# PCM2704_Test_v1B.net
KiCad netlist of a schematic drawn in EAGLE
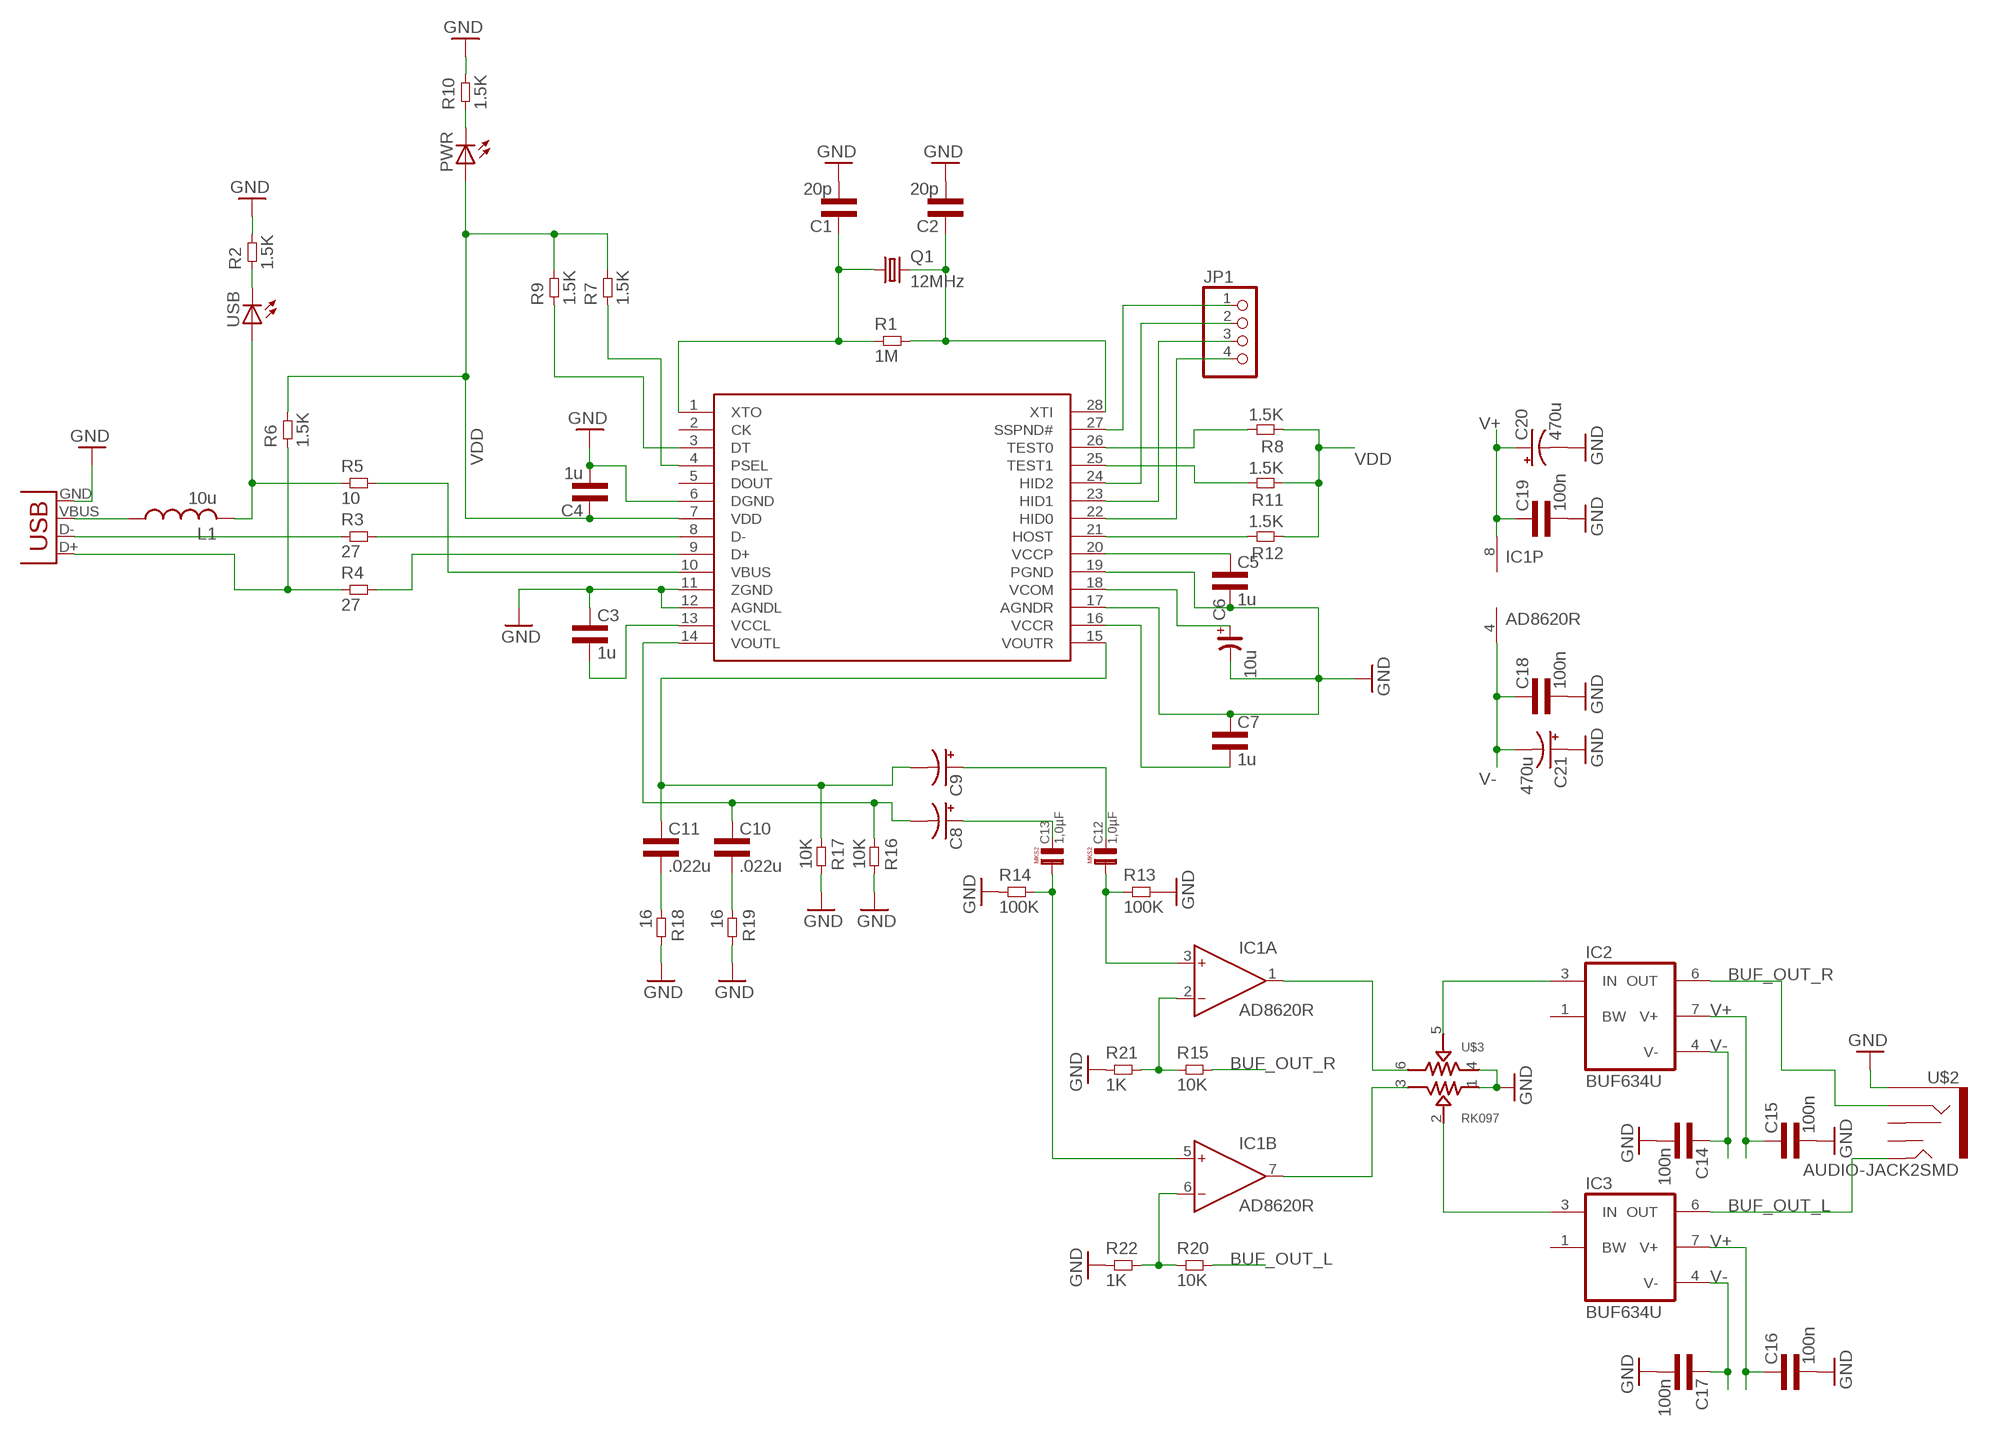
[diagram p0: schematic, sheet 1]

(export (version "E")
  (design (tool "Eeschema 10.0.6"))
  (components
    (comp (ref "C1")
      (value "20p")
      (footprint "eagle-import:0603L3")
      (libsource (lib "eagle-import") (part "CAP0603L3"))
    )
    (comp (ref "C2")
      (value "20p")
      (footprint "eagle-import:0603L3")
      (libsource (lib "eagle-import") (part "CAP0603L3"))
    )
    (comp (ref "C3")
      (value "1u")
      (footprint "eagle-import:0603L3")
      (libsource (lib "eagle-import") (part "CAP0603L3"))
    )
    (comp (ref "C4")
      (value "1u")
      (footprint "eagle-import:0603L3")
      (libsource (lib "eagle-import") (part "CAP0603L3"))
    )
    (comp (ref "C5")
      (value "1u")
      (footprint "eagle-import:0603L3")
      (libsource (lib "eagle-import") (part "CAP0603L3"))
    )
    (comp (ref "C6")
      (value "10u")
      (footprint "eagle-import:CE-010X030")
      (libsource (lib "eagle-import") (part "CP_E-010X030"))
    )
    (comp (ref "C7")
      (value "1u")
      (footprint "eagle-import:0603L3")
      (libsource (lib "eagle-import") (part "CAP0603L3"))
    )
    (comp (ref "C8")
      (value "CPOL-USE1.8-4")
      (footprint "eagle-import:E1,8-4")
      (libsource (lib "eagle-import") (part "CPOL-USE1.8-4"))
    )
    (comp (ref "C9")
      (value "CPOL-USE1.8-4")
      (footprint "eagle-import:E1,8-4")
      (libsource (lib "eagle-import") (part "CPOL-USE1.8-4"))
    )
    (comp (ref "C10")
      (value ".022u")
      (footprint "eagle-import:0603L3")
      (libsource (lib "eagle-import") (part "CAP0603L3"))
    )
    (comp (ref "C11")
      (value ".022u")
      (footprint "eagle-import:0603L3")
      (libsource (lib "eagle-import") (part "CAP0603L3"))
    )
    (comp (ref "C12")
      (value "1,0µF")
      (footprint "eagle-import:R5B5")
      (libsource (lib "eagle-import") (part "1,0µF"))
    )
    (comp (ref "C13")
      (value "1,0µF")
      (footprint "eagle-import:R5B5")
      (libsource (lib "eagle-import") (part "1,0µF"))
    )
    (comp (ref "C14")
      (value "100n")
      (footprint "eagle-import:0603L3")
      (libsource (lib "eagle-import") (part "CAP0603L3"))
    )
    (comp (ref "C15")
      (value "100n")
      (footprint "eagle-import:0603L3")
      (libsource (lib "eagle-import") (part "CAP0603L3"))
    )
    (comp (ref "C16")
      (value "100n")
      (footprint "eagle-import:0603L3")
      (libsource (lib "eagle-import") (part "CAP0603L3"))
    )
    (comp (ref "C17")
      (value "100n")
      (footprint "eagle-import:0603L3")
      (libsource (lib "eagle-import") (part "CAP0603L3"))
    )
    (comp (ref "C18")
      (value "100n")
      (footprint "eagle-import:0603L3")
      (libsource (lib "eagle-import") (part "CAP0603L3"))
    )
    (comp (ref "C19")
      (value "100n")
      (footprint "eagle-import:0603L3")
      (libsource (lib "eagle-import") (part "CAP0603L3"))
    )
    (comp (ref "C20")
      (value "470u")
      (footprint "eagle-import:E5-13")
      (libsource (lib "eagle-import") (part "CPOL-USE5-13"))
    )
    (comp (ref "C21")
      (value "470u")
      (footprint "eagle-import:E5-13")
      (libsource (lib "eagle-import") (part "CPOL-USE5-13"))
    )
    (comp (ref "IC1")
      (value "AD8620R")
      (footprint "eagle-import:SO8")
      (fields (field (name "MF") "ALTERA CORPORATION") (field (name "MPN") "AD8620ARZ"))
      (libsource (lib "eagle-import") (part "AD8620R"))
    )
    (comp (ref "IC2")
      (value "BUF634U")
      (footprint "eagle-import:SO08")
      (fields (field (name "MF") "TEXAS INSTRUMENTS"))
      (libsource (lib "eagle-import") (part "BUF634U"))
    )
    (comp (ref "IC3")
      (value "BUF634U")
      (footprint "eagle-import:SO08")
      (fields (field (name "MF") "TEXAS INSTRUMENTS"))
      (libsource (lib "eagle-import") (part "BUF634U"))
    )
    (comp (ref "JP1")
      (value "PINHD-1X4")
      (footprint "eagle-import:1X04")
      (libsource (lib "eagle-import") (part "PINHD-1X4"))
    )
    (comp (ref "L1")
      (value "10u")
      (footprint "eagle-import:L3225M")
      (libsource (lib "eagle-import") (part "L-USL3225M"))
    )
    (comp (ref "PWR")
      (value "LEDCHIP-LED0603")
      (footprint "eagle-import:CHIP-LED0603")
      (libsource (lib "eagle-import") (part "LEDCHIP-LED0603"))
    )
    (comp (ref "Q1")
      (value "12MHz")
      (footprint "eagle-import:HC49US")
      (libsource (lib "eagle-import") (part "CRYSTALHC49US"))
    )
    (comp (ref "R1")
      (value "1M")
      (footprint "eagle-import:0603L3")
      (libsource (lib "eagle-import") (part "RES0603L3"))
    )
    (comp (ref "R2")
      (value "1.5K")
      (footprint "eagle-import:0603L3")
      (libsource (lib "eagle-import") (part "RES0603L3"))
    )
    (comp (ref "R3")
      (value "27")
      (footprint "eagle-import:0603L3")
      (libsource (lib "eagle-import") (part "RES0603L3"))
    )
    (comp (ref "R4")
      (value "27")
      (footprint "eagle-import:0603L3")
      (libsource (lib "eagle-import") (part "RES0603L3"))
    )
    (comp (ref "R5")
      (value "10")
      (footprint "eagle-import:0805L3")
      (libsource (lib "eagle-import") (part "RES0805L3"))
    )
    (comp (ref "R6")
      (value "1.5K")
      (footprint "eagle-import:0603L3")
      (libsource (lib "eagle-import") (part "RES0603L3"))
    )
    (comp (ref "R7")
      (value "1.5K")
      (footprint "eagle-import:0603L3")
      (libsource (lib "eagle-import") (part "RES0603L3"))
    )
    (comp (ref "R8")
      (value "1.5K")
      (footprint "eagle-import:0603L3")
      (libsource (lib "eagle-import") (part "RES0603L3"))
    )
    (comp (ref "R9")
      (value "1.5K")
      (footprint "eagle-import:0603L3")
      (libsource (lib "eagle-import") (part "RES0603L3"))
    )
    (comp (ref "R10")
      (value "1.5K")
      (footprint "eagle-import:0603L3")
      (libsource (lib "eagle-import") (part "RES0603L3"))
    )
    (comp (ref "R11")
      (value "1.5K")
      (footprint "eagle-import:0603L3")
      (libsource (lib "eagle-import") (part "RES0603L3"))
    )
    (comp (ref "R12")
      (value "1.5K")
      (footprint "eagle-import:0603L3")
      (libsource (lib "eagle-import") (part "RES0603L3"))
    )
    (comp (ref "R13")
      (value "100K")
      (footprint "eagle-import:0603L3")
      (libsource (lib "eagle-import") (part "RES0603L3"))
    )
    (comp (ref "R14")
      (value "100K")
      (footprint "eagle-import:0603L3")
      (libsource (lib "eagle-import") (part "RES0603L3"))
    )
    (comp (ref "R15")
      (value "10K")
      (footprint "eagle-import:0603L3")
      (libsource (lib "eagle-import") (part "RES0603L3"))
    )
    (comp (ref "R16")
      (value "10K")
      (footprint "eagle-import:0603L3")
      (libsource (lib "eagle-import") (part "RES0603L3"))
    )
    (comp (ref "R17")
      (value "10K")
      (footprint "eagle-import:0603L3")
      (libsource (lib "eagle-import") (part "RES0603L3"))
    )
    (comp (ref "R18")
      (value "16")
      (footprint "eagle-import:0603L3")
      (libsource (lib "eagle-import") (part "RES0603L3"))
    )
    (comp (ref "R19")
      (value "16")
      (footprint "eagle-import:0603L3")
      (libsource (lib "eagle-import") (part "RES0603L3"))
    )
    (comp (ref "R20")
      (value "10K")
      (footprint "eagle-import:0603L3")
      (libsource (lib "eagle-import") (part "RES0603L3"))
    )
    (comp (ref "R21")
      (value "1K")
      (footprint "eagle-import:0603L3")
      (libsource (lib "eagle-import") (part "RES0603L3"))
    )
    (comp (ref "R22")
      (value "1K")
      (footprint "eagle-import:0603L3")
      (libsource (lib "eagle-import") (part "RES0603L3"))
    )
    (comp (ref "U$1")
      (value "PCM2704C")
      (footprint "eagle-import:PCM2704C")
      (libsource (lib "eagle-import") (part "PCM2704C"))
    )
    (comp (ref "U$2")
      (value "AUDIO-JACK2SMD")
      (footprint "eagle-import:AUDIO-JACK-3.5MM-SMD")
      (libsource (lib "eagle-import") (part "AUDIO-JACK2SMD"))
    )
    (comp (ref "U$3")
      (value "RK097")
      (footprint "eagle-import:RK097")
      (libsource (lib "eagle-import") (part "RK097"))
    )
    (comp (ref "USB")
      (value "LEDCHIP-LED0603")
      (footprint "eagle-import:CHIP-LED0603")
      (libsource (lib "eagle-import") (part "LEDCHIP-LED0603"))
    )
    (comp (ref "X1")
      (value "USB-MB-S")
      (footprint "eagle-import:USB-MB-S")
      (libsource (lib "eagle-import") (part "USB-MB-S"))
    )
  )
  (nets
    (net (code "1") (name "/BUF_OUT_L") (class "Default")
      (node (ref "IC3") (pin "6") (pinfunction "OUT_6") (pintype "output"))
      (node (ref "R20") (pin "P$2") (pinfunction "2_P$2") (pintype "bidirectional"))
      (node (ref "U$2") (pin "TIP") (pinfunction "TIP_TIP") (pintype "bidirectional"))
    )
    (net (code "2") (name "/BUF_OUT_R") (class "Default")
      (node (ref "IC2") (pin "6") (pinfunction "OUT_6") (pintype "output"))
      (node (ref "R15") (pin "P$2") (pinfunction "2_P$2") (pintype "bidirectional"))
      (node (ref "U$2") (pin "RING") (pinfunction "RING_RING") (pintype "bidirectional"))
    )
    (net (code "3") (name "/V+") (class "Default")
      (node (ref "C15") (pin "P$1") (pinfunction "1_P$1") (pintype "bidirectional"))
      (node (ref "C16") (pin "P$1") (pinfunction "1_P$1") (pintype "bidirectional"))
      (node (ref "C19") (pin "P$1") (pinfunction "1_P$1") (pintype "bidirectional"))
      (node (ref "C20") (pin "+") (pinfunction "+_+") (pintype "passive"))
      (node (ref "IC1") (pin "8") (pinfunction "V+_8") (pintype "power_in"))
      (node (ref "IC2") (pin "7") (pinfunction "V+_7") (pintype "power_in"))
      (node (ref "IC3") (pin "7") (pinfunction "V+_7") (pintype "power_in"))
    )
    (net (code "4") (name "/V-") (class "Default")
      (node (ref "C14") (pin "P$1") (pinfunction "1_P$1") (pintype "bidirectional"))
      (node (ref "C17") (pin "P$1") (pinfunction "1_P$1") (pintype "bidirectional"))
      (node (ref "C18") (pin "P$1") (pinfunction "1_P$1") (pintype "bidirectional"))
      (node (ref "C21") (pin "-") (pinfunction "-_-") (pintype "passive"))
      (node (ref "IC1") (pin "4") (pinfunction "V-_4") (pintype "power_in"))
      (node (ref "IC2") (pin "4") (pinfunction "V-_4") (pintype "power_in"))
      (node (ref "IC3") (pin "4") (pinfunction "V-_4") (pintype "power_in"))
    )
    (net (code "5") (name "/VDD") (class "Default")
      (node (ref "C4") (pin "P$1") (pinfunction "1_P$1") (pintype "bidirectional"))
      (node (ref "PWR") (pin "A") (pinfunction "A_A") (pintype "passive"))
      (node (ref "R11") (pin "P$1") (pinfunction "1_P$1") (pintype "bidirectional"))
      (node (ref "R12") (pin "P$1") (pinfunction "1_P$1") (pintype "bidirectional"))
      (node (ref "R6") (pin "P$2") (pinfunction "2_P$2") (pintype "bidirectional"))
      (node (ref "R7") (pin "P$2") (pinfunction "2_P$2") (pintype "bidirectional"))
      (node (ref "R8") (pin "P$1") (pinfunction "1_P$1") (pintype "bidirectional"))
      (node (ref "R9") (pin "P$2") (pinfunction "2_P$2") (pintype "bidirectional"))
      (node (ref "U$1") (pin "7") (pinfunction "VDD_7") (pintype "bidirectional"))
    )
    (net (code "6") (name "GND") (class "Default")
      (node (ref "C1") (pin "P$2") (pinfunction "2_P$2") (pintype "bidirectional"))
      (node (ref "C14") (pin "P$2") (pinfunction "2_P$2") (pintype "bidirectional"))
      (node (ref "C15") (pin "P$2") (pinfunction "2_P$2") (pintype "bidirectional"))
      (node (ref "C16") (pin "P$2") (pinfunction "2_P$2") (pintype "bidirectional"))
      (node (ref "C17") (pin "P$2") (pinfunction "2_P$2") (pintype "bidirectional"))
      (node (ref "C18") (pin "P$2") (pinfunction "2_P$2") (pintype "bidirectional"))
      (node (ref "C19") (pin "P$2") (pinfunction "2_P$2") (pintype "bidirectional"))
      (node (ref "C2") (pin "P$2") (pinfunction "2_P$2") (pintype "bidirectional"))
      (node (ref "C20") (pin "-") (pinfunction "-_-") (pintype "passive"))
      (node (ref "C21") (pin "+") (pinfunction "+_+") (pintype "passive"))
      (node (ref "C3") (pin "P$1") (pinfunction "1_P$1") (pintype "bidirectional"))
      (node (ref "C4") (pin "P$2") (pinfunction "2_P$2") (pintype "bidirectional"))
      (node (ref "C5") (pin "P$2") (pinfunction "2_P$2") (pintype "bidirectional"))
      (node (ref "C6") (pin "-") (pinfunction "-_-") (pintype "passive"))
      (node (ref "C7") (pin "P$1") (pinfunction "1_P$1") (pintype "bidirectional"))
      (node (ref "R10") (pin "P$2") (pinfunction "2_P$2") (pintype "bidirectional"))
      (node (ref "R13") (pin "P$2") (pinfunction "2_P$2") (pintype "bidirectional"))
      (node (ref "R14") (pin "P$1") (pinfunction "1_P$1") (pintype "bidirectional"))
      (node (ref "R16") (pin "P$2") (pinfunction "2_P$2") (pintype "bidirectional"))
      (node (ref "R17") (pin "P$2") (pinfunction "2_P$2") (pintype "bidirectional"))
      (node (ref "R18") (pin "P$2") (pinfunction "2_P$2") (pintype "bidirectional"))
      (node (ref "R19") (pin "P$2") (pinfunction "2_P$2") (pintype "bidirectional"))
      (node (ref "R2") (pin "P$2") (pinfunction "2_P$2") (pintype "bidirectional"))
      (node (ref "R21") (pin "P$1") (pinfunction "1_P$1") (pintype "bidirectional"))
      (node (ref "R22") (pin "P$1") (pinfunction "1_P$1") (pintype "bidirectional"))
      (node (ref "U$1") (pin "11") (pinfunction "ZGND_11") (pintype "bidirectional"))
      (node (ref "U$1") (pin "12") (pinfunction "AGNDL_12") (pintype "bidirectional"))
      (node (ref "U$1") (pin "17") (pinfunction "AGNDR_17") (pintype "bidirectional"))
      (node (ref "U$1") (pin "19") (pinfunction "PGND_19") (pintype "bidirectional"))
      (node (ref "U$1") (pin "6") (pinfunction "DGND_6") (pintype "bidirectional"))
      (node (ref "U$2") (pin "SLEEVE") (pinfunction "SLEEVE_SLEEVE") (pintype "bidirectional"))
      (node (ref "U$3") (pin "1") (pinfunction "1_1") (pintype "bidirectional"))
      (node (ref "U$3") (pin "4") (pinfunction "4_4") (pintype "bidirectional"))
      (node (ref "X1") (pin "GND") (pinfunction "GND_GND") (pintype "bidirectional"))
    )
    (net (code "7") (name "Net-(C1-1)") (class "Default")
      (node (ref "C1") (pin "P$1") (pinfunction "1_P$1") (pintype "bidirectional"))
      (node (ref "Q1") (pin "1") (pinfunction "1_1") (pintype "passive"))
      (node (ref "R1") (pin "P$1") (pinfunction "1_P$1") (pintype "bidirectional"))
      (node (ref "U$1") (pin "1") (pinfunction "XTO_1") (pintype "bidirectional"))
    )
    (net (code "8") (name "Net-(C2-1)") (class "Default")
      (node (ref "C2") (pin "P$1") (pinfunction "1_P$1") (pintype "bidirectional"))
      (node (ref "Q1") (pin "2") (pinfunction "2_2") (pintype "passive"))
      (node (ref "R1") (pin "P$2") (pinfunction "2_P$2") (pintype "bidirectional"))
      (node (ref "U$1") (pin "28") (pinfunction "XTI_28") (pintype "bidirectional"))
    )
    (net (code "9") (name "Net-(C3-2)") (class "Default")
      (node (ref "C3") (pin "P$2") (pinfunction "2_P$2") (pintype "bidirectional"))
      (node (ref "U$1") (pin "13") (pinfunction "VCCL_13") (pintype "bidirectional"))
    )
    (net (code "10") (name "Net-(C5-1)") (class "Default")
      (node (ref "C5") (pin "P$1") (pinfunction "1_P$1") (pintype "bidirectional"))
      (node (ref "U$1") (pin "20") (pinfunction "VCCP_20") (pintype "bidirectional"))
    )
    (net (code "11") (name "Net-(C7-2)") (class "Default")
      (node (ref "C7") (pin "P$2") (pinfunction "2_P$2") (pintype "bidirectional"))
      (node (ref "U$1") (pin "16") (pinfunction "VCCR_16") (pintype "bidirectional"))
    )
    (net (code "12") (name "Net-(C10-1)") (class "Default")
      (node (ref "C10") (pin "P$1") (pinfunction "1_P$1") (pintype "bidirectional"))
      (node (ref "C8") (pin "-") (pinfunction "-_-") (pintype "passive"))
      (node (ref "R16") (pin "P$1") (pinfunction "1_P$1") (pintype "bidirectional"))
      (node (ref "U$1") (pin "14") (pinfunction "VOUTL_14") (pintype "bidirectional"))
    )
    (net (code "13") (name "Net-(C10-2)") (class "Default")
      (node (ref "C10") (pin "P$2") (pinfunction "2_P$2") (pintype "bidirectional"))
      (node (ref "R19") (pin "P$1") (pinfunction "1_P$1") (pintype "bidirectional"))
    )
    (net (code "14") (name "Net-(C11-1)") (class "Default")
      (node (ref "C11") (pin "P$1") (pinfunction "1_P$1") (pintype "bidirectional"))
      (node (ref "C9") (pin "-") (pinfunction "-_-") (pintype "passive"))
      (node (ref "R17") (pin "P$1") (pinfunction "1_P$1") (pintype "bidirectional"))
      (node (ref "U$1") (pin "15") (pinfunction "VOUTR_15") (pintype "bidirectional"))
    )
    (net (code "15") (name "Net-(C11-2)") (class "Default")
      (node (ref "C11") (pin "P$2") (pinfunction "2_P$2") (pintype "bidirectional"))
      (node (ref "R18") (pin "P$1") (pinfunction "1_P$1") (pintype "bidirectional"))
    )
    (net (code "16") (name "Net-(C12-Pad2)") (class "Default")
      (node (ref "C12") (pin "2") (pinfunction "2_2") (pintype "passive"))
      (node (ref "C9") (pin "+") (pinfunction "+_+") (pintype "passive"))
    )
    (net (code "17") (name "Net-(C13-Pad2)") (class "Default")
      (node (ref "C13") (pin "2") (pinfunction "2_2") (pintype "passive"))
      (node (ref "C8") (pin "+") (pinfunction "+_+") (pintype "passive"))
    )
    (net (code "18") (name "Net-(IC1A-IN+)") (class "Default")
      (node (ref "C12") (pin "1") (pinfunction "1_1") (pintype "passive"))
      (node (ref "IC1") (pin "3") (pinfunction "IN+_3") (pintype "input"))
      (node (ref "R13") (pin "P$1") (pinfunction "1_P$1") (pintype "bidirectional"))
    )
    (net (code "19") (name "Net-(IC1A-IN-)") (class "Default")
      (node (ref "IC1") (pin "2") (pinfunction "IN-_2") (pintype "input"))
      (node (ref "R15") (pin "P$1") (pinfunction "1_P$1") (pintype "bidirectional"))
      (node (ref "R21") (pin "P$2") (pinfunction "2_P$2") (pintype "bidirectional"))
    )
    (net (code "20") (name "Net-(IC1A-OUT)") (class "Default")
      (node (ref "IC1") (pin "1") (pinfunction "OUT_1") (pintype "output"))
      (node (ref "U$3") (pin "6") (pinfunction "6_6") (pintype "bidirectional"))
    )
    (net (code "21") (name "Net-(IC1B-IN+)") (class "Default")
      (node (ref "C13") (pin "1") (pinfunction "1_1") (pintype "passive"))
      (node (ref "IC1") (pin "5") (pinfunction "IN+_5") (pintype "input"))
      (node (ref "R14") (pin "P$2") (pinfunction "2_P$2") (pintype "bidirectional"))
    )
    (net (code "22") (name "Net-(IC1B-IN-)") (class "Default")
      (node (ref "IC1") (pin "6") (pinfunction "IN-_6") (pintype "input"))
      (node (ref "R20") (pin "P$1") (pinfunction "1_P$1") (pintype "bidirectional"))
      (node (ref "R22") (pin "P$2") (pinfunction "2_P$2") (pintype "bidirectional"))
    )
    (net (code "23") (name "Net-(IC1B-OUT)") (class "Default")
      (node (ref "IC1") (pin "7") (pinfunction "OUT_7") (pintype "output"))
      (node (ref "U$3") (pin "3") (pinfunction "3_3") (pintype "bidirectional"))
    )
    (net (code "24") (name "Net-(IC2-IN)") (class "Default")
      (node (ref "IC2") (pin "3") (pinfunction "IN_3") (pintype "input"))
      (node (ref "U$3") (pin "5") (pinfunction "5_5") (pintype "bidirectional"))
    )
    (net (code "25") (name "Net-(IC3-IN)") (class "Default")
      (node (ref "IC3") (pin "3") (pinfunction "IN_3") (pintype "input"))
      (node (ref "U$3") (pin "2") (pinfunction "2_2") (pintype "bidirectional"))
    )
    (net (code "26") (name "Net-(L1-Pad1)") (class "Default")
      (node (ref "L1") (pin "1") (pinfunction "1_1") (pintype "passive"))
      (node (ref "X1") (pin "VBUS") (pinfunction "VBUS_VBUS") (pintype "bidirectional"))
    )
    (net (code "27") (name "Net-(L1-Pad2)") (class "Default")
      (node (ref "L1") (pin "2") (pinfunction "2_2") (pintype "passive"))
      (node (ref "R5") (pin "1") (pinfunction "1_1") (pintype "bidirectional"))
      (node (ref "USB") (pin "A") (pinfunction "A_A") (pintype "passive"))
    )
    (net (code "28") (name "Net-(R2-1)") (class "Default")
      (node (ref "R2") (pin "P$1") (pinfunction "1_P$1") (pintype "bidirectional"))
      (node (ref "USB") (pin "C") (pinfunction "C_C") (pintype "passive"))
    )
    (net (code "29") (name "Net-(R3-1)") (class "Default")
      (node (ref "R3") (pin "P$1") (pinfunction "1_P$1") (pintype "bidirectional"))
      (node (ref "X1") (pin "D-") (pinfunction "D-_D-") (pintype "bidirectional"))
    )
    (net (code "30") (name "Net-(R3-2)") (class "Default")
      (node (ref "R3") (pin "P$2") (pinfunction "2_P$2") (pintype "bidirectional"))
      (node (ref "U$1") (pin "8") (pinfunction "D-_8") (pintype "bidirectional"))
    )
    (net (code "31") (name "Net-(R4-1)") (class "Default")
      (node (ref "R4") (pin "P$1") (pinfunction "1_P$1") (pintype "bidirectional"))
      (node (ref "R6") (pin "P$1") (pinfunction "1_P$1") (pintype "bidirectional"))
      (node (ref "X1") (pin "D+") (pinfunction "D+_D+") (pintype "bidirectional"))
    )
    (net (code "32") (name "Net-(R4-2)") (class "Default")
      (node (ref "R4") (pin "P$2") (pinfunction "2_P$2") (pintype "bidirectional"))
      (node (ref "U$1") (pin "9") (pinfunction "D+_9") (pintype "bidirectional"))
    )
    (net (code "33") (name "Net-(R7-1)") (class "Default")
      (node (ref "R7") (pin "P$1") (pinfunction "1_P$1") (pintype "bidirectional"))
      (node (ref "U$1") (pin "4") (pinfunction "PSEL_4") (pintype "bidirectional"))
    )
    (net (code "34") (name "Net-(R8-2)") (class "Default")
      (node (ref "R8") (pin "P$2") (pinfunction "2_P$2") (pintype "bidirectional"))
      (node (ref "U$1") (pin "26") (pinfunction "TEST0_26") (pintype "bidirectional"))
    )
    (net (code "35") (name "Net-(R9-1)") (class "Default")
      (node (ref "R9") (pin "P$1") (pinfunction "1_P$1") (pintype "bidirectional"))
      (node (ref "U$1") (pin "3") (pinfunction "DT_3") (pintype "bidirectional"))
    )
    (net (code "36") (name "Net-(R10-1)") (class "Default")
      (node (ref "PWR") (pin "C") (pinfunction "C_C") (pintype "passive"))
      (node (ref "R10") (pin "P$1") (pinfunction "1_P$1") (pintype "bidirectional"))
    )
    (net (code "37") (name "Net-(R11-2)") (class "Default")
      (node (ref "R11") (pin "P$2") (pinfunction "2_P$2") (pintype "bidirectional"))
      (node (ref "U$1") (pin "25") (pinfunction "TEST1_25") (pintype "bidirectional"))
    )
    (net (code "38") (name "Net-(R12-2)") (class "Default")
      (node (ref "R12") (pin "P$2") (pinfunction "2_P$2") (pintype "bidirectional"))
      (node (ref "U$1") (pin "21") (pinfunction "HOST_21") (pintype "bidirectional"))
    )
    (net (code "39") (name "Net-(U$1-HID0)") (class "Default")
      (node (ref "JP1") (pin "4") (pinfunction "4_4") (pintype "passive"))
      (node (ref "U$1") (pin "22") (pinfunction "HID0_22") (pintype "bidirectional"))
    )
    (net (code "40") (name "Net-(U$1-HID1)") (class "Default")
      (node (ref "JP1") (pin "3") (pinfunction "3_3") (pintype "passive"))
      (node (ref "U$1") (pin "23") (pinfunction "HID1_23") (pintype "bidirectional"))
    )
    (net (code "41") (name "Net-(U$1-HID2)") (class "Default")
      (node (ref "JP1") (pin "2") (pinfunction "2_2") (pintype "passive"))
      (node (ref "U$1") (pin "24") (pinfunction "HID2_24") (pintype "bidirectional"))
    )
    (net (code "42") (name "Net-(U$1-SSPND#)") (class "Default")
      (node (ref "JP1") (pin "1") (pinfunction "1_1") (pintype "passive"))
      (node (ref "U$1") (pin "27") (pinfunction "SSPND#_27") (pintype "bidirectional"))
    )
    (net (code "43") (name "Net-(U$1-VBUS)") (class "Default")
      (node (ref "R5") (pin "2") (pinfunction "2_2") (pintype "bidirectional"))
      (node (ref "U$1") (pin "10") (pinfunction "VBUS_10") (pintype "bidirectional"))
    )
    (net (code "44") (name "Net-(U$1-VCOM)") (class "Default")
      (node (ref "C6") (pin "+") (pinfunction "+_+") (pintype "passive"))
      (node (ref "U$1") (pin "18") (pinfunction "VCOM_18") (pintype "bidirectional"))
    )
    (net (code "45") (name "unconnected-(IC2-BW-Pad1)") (class "Default")
      (node (ref "IC2") (pin "1") (pinfunction "BW_1") (pintype "passive"))
    )
    (net (code "46") (name "unconnected-(IC3-BW-Pad1)") (class "Default")
      (node (ref "IC3") (pin "1") (pinfunction "BW_1") (pintype "passive"))
    )
    (net (code "47") (name "unconnected-(U$1-CK-Pad2)") (class "Default")
      (node (ref "U$1") (pin "2") (pinfunction "CK_2") (pintype "bidirectional"))
    )
    (net (code "48") (name "unconnected-(U$1-DOUT-Pad5)") (class "Default")
      (node (ref "U$1") (pin "5") (pinfunction "DOUT_5") (pintype "bidirectional"))
    )
    (net (code "49") (name "unconnected-(U$2-PadRSH)") (class "Default")
      (node (ref "U$2") (pin "RSH") (pinfunction "RSH_RSH") (pintype "bidirectional"))
    )
    (net (code "50") (name "unconnected-(U$2-PadTSH)") (class "Default")
      (node (ref "U$2") (pin "TSH") (pinfunction "TSH_TSH") (pintype "bidirectional"))
    )
  )
)
